# tdt_switch.net
KiCad netlist of a schematic drawn in EAGLE
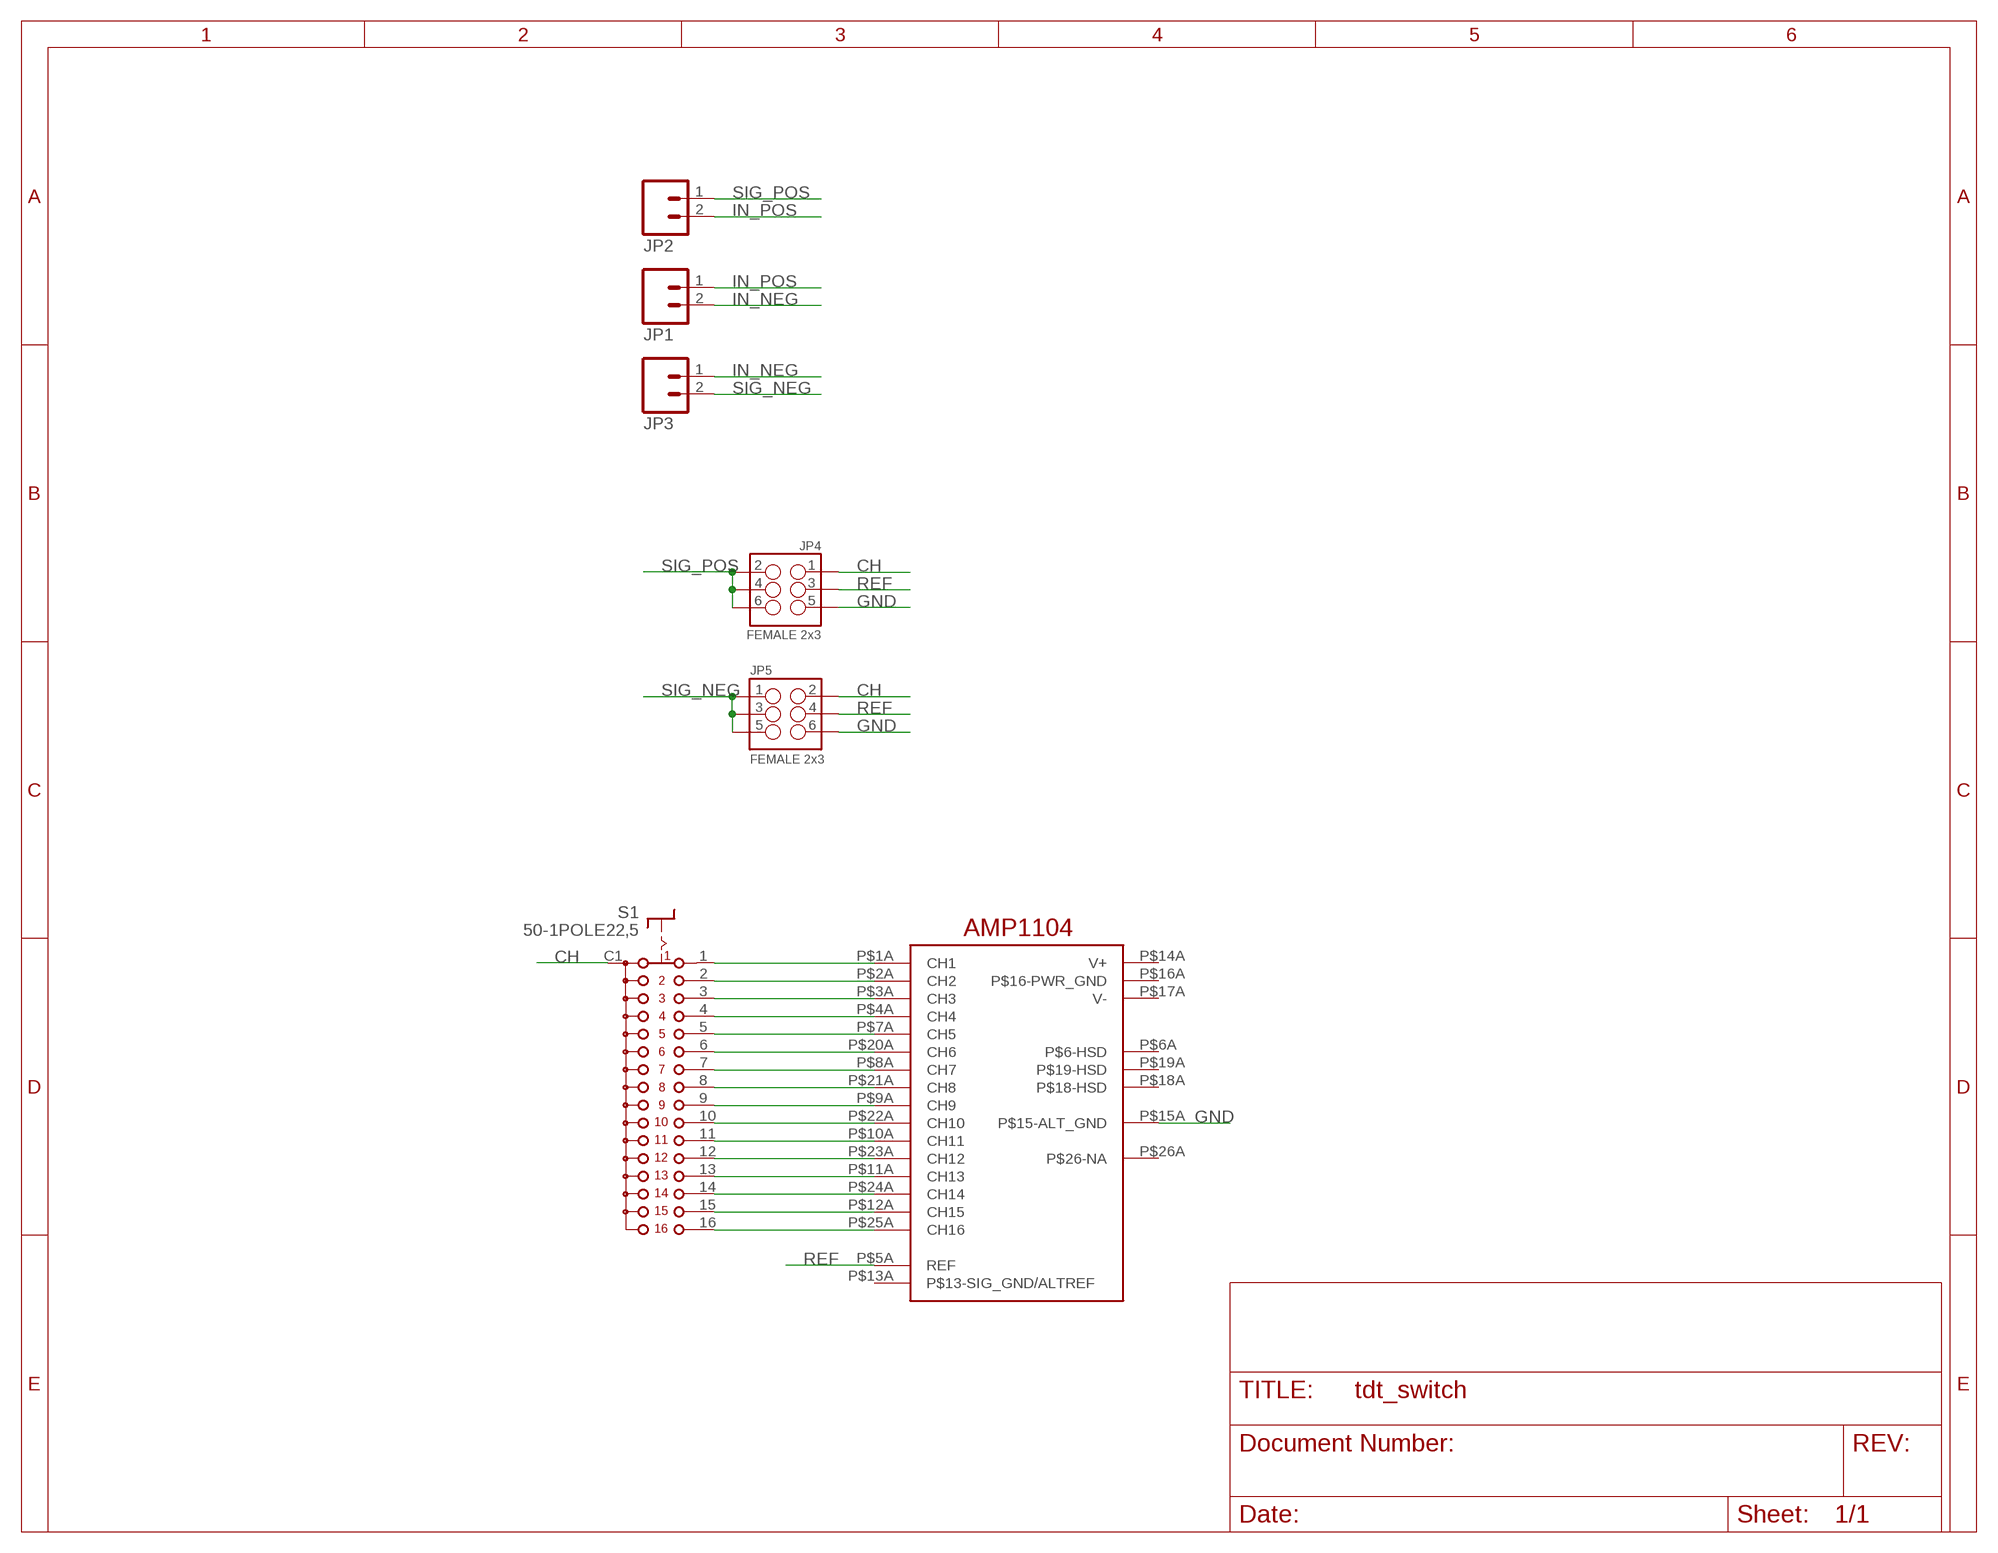
[diagram p0: schematic, sheet 1]

(export (version "E")
  (design (tool "Eeschema 10.0.6"))
  (components
    (comp (ref "JP1")
      (value "M02PTH")
      (footprint "eagle-import:1X02")
      (libsource (lib "eagle-import") (part "M02PTH"))
    )
    (comp (ref "JP2")
      (value "M02PTH")
      (footprint "eagle-import:1X02")
      (libsource (lib "eagle-import") (part "M02PTH"))
    )
    (comp (ref "JP3")
      (value "M02PTH")
      (footprint "eagle-import:1X02")
      (libsource (lib "eagle-import") (part "M02PTH"))
    )
    (comp (ref "JP4")
      (value "FEMALE 2x3")
      (footprint "eagle-import:2X3")
      (libsource (lib "eagle-import") (part "M03X2FEMALE"))
    )
    (comp (ref "JP5")
      (value "FEMALE 2x3")
      (footprint "eagle-import:2X3")
      (libsource (lib "eagle-import") (part "M03X2FEMALE"))
    )
    (comp (ref "S1")
      (value "50-1POLE22,5")
      (footprint "eagle-import:50-1POLE22,5")
      (libsource (lib "eagle-import") (part "50-1POLE22,5"))
    )
    (comp (ref "U$3")
      (value "AMP1104")
      (footprint "eagle-import:AMP1104")
      (libsource (lib "eagle-import") (part "AMP1104"))
    )
  )
  (nets
    (net (code "1") (name "/CH") (class "Default")
      (node (ref "JP4") (pin "1") (pinfunction "1_1") (pintype "bidirectional"))
      (node (ref "JP5") (pin "2") (pinfunction "2_2") (pintype "bidirectional"))
      (node (ref "S1") (pin "C1") (pinfunction "C_C1") (pintype "passive"))
    )
    (net (code "2") (name "/GND") (class "Default")
      (node (ref "JP4") (pin "5") (pinfunction "5_5") (pintype "bidirectional"))
      (node (ref "JP5") (pin "6") (pinfunction "6_6") (pintype "bidirectional"))
      (node (ref "U$3") (pin "P$15A") (pinfunction "P$15-ALT_GND_P$15A") (pintype "bidirectional"))
    )
    (net (code "3") (name "/IN_NEG") (class "Default")
      (node (ref "JP1") (pin "2") (pinfunction "2_2") (pintype "passive"))
      (node (ref "JP3") (pin "1") (pinfunction "1_1") (pintype "passive"))
    )
    (net (code "4") (name "/IN_POS") (class "Default")
      (node (ref "JP1") (pin "1") (pinfunction "1_1") (pintype "passive"))
      (node (ref "JP2") (pin "2") (pinfunction "2_2") (pintype "passive"))
    )
    (net (code "5") (name "/REF") (class "Default")
      (node (ref "JP4") (pin "3") (pinfunction "3_3") (pintype "bidirectional"))
      (node (ref "JP5") (pin "4") (pinfunction "4_4") (pintype "bidirectional"))
      (node (ref "U$3") (pin "P$5A") (pinfunction "REF_P$5A") (pintype "bidirectional"))
    )
    (net (code "6") (name "/SIG_NEG") (class "Default")
      (node (ref "JP3") (pin "2") (pinfunction "2_2") (pintype "passive"))
      (node (ref "JP5") (pin "1") (pinfunction "1_1") (pintype "bidirectional"))
      (node (ref "JP5") (pin "3") (pinfunction "3_3") (pintype "bidirectional"))
      (node (ref "JP5") (pin "5") (pinfunction "5_5") (pintype "bidirectional"))
    )
    (net (code "7") (name "/SIG_POS") (class "Default")
      (node (ref "JP2") (pin "1") (pinfunction "1_1") (pintype "passive"))
      (node (ref "JP4") (pin "2") (pinfunction "2_2") (pintype "bidirectional"))
      (node (ref "JP4") (pin "4") (pinfunction "4_4") (pintype "bidirectional"))
      (node (ref "JP4") (pin "6") (pinfunction "6_6") (pintype "bidirectional"))
    )
    (net (code "8") (name "Net-(U$3-CH1)") (class "Default")
      (node (ref "S1") (pin "1") (pinfunction "1_1") (pintype "passive"))
      (node (ref "U$3") (pin "P$1A") (pinfunction "CH1_P$1A") (pintype "bidirectional"))
    )
    (net (code "9") (name "Net-(U$3-CH2)") (class "Default")
      (node (ref "S1") (pin "2") (pinfunction "2_2") (pintype "passive"))
      (node (ref "U$3") (pin "P$2A") (pinfunction "CH2_P$2A") (pintype "bidirectional"))
    )
    (net (code "10") (name "Net-(U$3-CH3)") (class "Default")
      (node (ref "S1") (pin "3") (pinfunction "3_3") (pintype "passive"))
      (node (ref "U$3") (pin "P$3A") (pinfunction "CH3_P$3A") (pintype "bidirectional"))
    )
    (net (code "11") (name "Net-(U$3-CH4)") (class "Default")
      (node (ref "S1") (pin "4") (pinfunction "4_4") (pintype "passive"))
      (node (ref "U$3") (pin "P$4A") (pinfunction "CH4_P$4A") (pintype "bidirectional"))
    )
    (net (code "12") (name "Net-(U$3-CH5)") (class "Default")
      (node (ref "S1") (pin "5") (pinfunction "5_5") (pintype "passive"))
      (node (ref "U$3") (pin "P$7A") (pinfunction "CH5_P$7A") (pintype "bidirectional"))
    )
    (net (code "13") (name "Net-(U$3-CH6)") (class "Default")
      (node (ref "S1") (pin "6") (pinfunction "6_6") (pintype "passive"))
      (node (ref "U$3") (pin "P$20A") (pinfunction "CH6_P$20A") (pintype "bidirectional"))
    )
    (net (code "14") (name "Net-(U$3-CH7)") (class "Default")
      (node (ref "S1") (pin "7") (pinfunction "7_7") (pintype "passive"))
      (node (ref "U$3") (pin "P$8A") (pinfunction "CH7_P$8A") (pintype "bidirectional"))
    )
    (net (code "15") (name "Net-(U$3-CH8)") (class "Default")
      (node (ref "S1") (pin "8") (pinfunction "8_8") (pintype "passive"))
      (node (ref "U$3") (pin "P$21A") (pinfunction "CH8_P$21A") (pintype "bidirectional"))
    )
    (net (code "16") (name "Net-(U$3-CH9)") (class "Default")
      (node (ref "S1") (pin "9") (pinfunction "9_9") (pintype "passive"))
      (node (ref "U$3") (pin "P$9A") (pinfunction "CH9_P$9A") (pintype "bidirectional"))
    )
    (net (code "17") (name "Net-(U$3-CH10)") (class "Default")
      (node (ref "S1") (pin "10") (pinfunction "10_10") (pintype "passive"))
      (node (ref "U$3") (pin "P$22A") (pinfunction "CH10_P$22A") (pintype "bidirectional"))
    )
    (net (code "18") (name "Net-(U$3-CH11)") (class "Default")
      (node (ref "S1") (pin "11") (pinfunction "11_11") (pintype "passive"))
      (node (ref "U$3") (pin "P$10A") (pinfunction "CH11_P$10A") (pintype "bidirectional"))
    )
    (net (code "19") (name "Net-(U$3-CH12)") (class "Default")
      (node (ref "S1") (pin "12") (pinfunction "12_12") (pintype "passive"))
      (node (ref "U$3") (pin "P$23A") (pinfunction "CH12_P$23A") (pintype "bidirectional"))
    )
    (net (code "20") (name "Net-(U$3-CH13)") (class "Default")
      (node (ref "S1") (pin "13") (pinfunction "13_13") (pintype "passive"))
      (node (ref "U$3") (pin "P$11A") (pinfunction "CH13_P$11A") (pintype "bidirectional"))
    )
    (net (code "21") (name "Net-(U$3-CH14)") (class "Default")
      (node (ref "S1") (pin "14") (pinfunction "14_14") (pintype "passive"))
      (node (ref "U$3") (pin "P$24A") (pinfunction "CH14_P$24A") (pintype "bidirectional"))
    )
    (net (code "22") (name "Net-(U$3-CH15)") (class "Default")
      (node (ref "S1") (pin "15") (pinfunction "15_15") (pintype "passive"))
      (node (ref "U$3") (pin "P$12A") (pinfunction "CH15_P$12A") (pintype "bidirectional"))
    )
    (net (code "23") (name "Net-(U$3-CH16)") (class "Default")
      (node (ref "S1") (pin "16") (pinfunction "16_16") (pintype "passive"))
      (node (ref "U$3") (pin "P$25A") (pinfunction "CH16_P$25A") (pintype "bidirectional"))
    )
    (net (code "24") (name "unconnected-(U$3-P$6-HSD-PadP$6A)") (class "Default")
      (node (ref "U$3") (pin "P$6A") (pinfunction "P$6-HSD_P$6A") (pintype "bidirectional"))
    )
    (net (code "25") (name "unconnected-(U$3-P$13-SIG_GND{slash}ALTREF-PadP$13A)") (class "Default")
      (node (ref "U$3") (pin "P$13A") (pinfunction "P$13-SIG_GND/ALTREF_P$13A") (pintype "bidirectional"))
    )
    (net (code "26") (name "unconnected-(U$3-P$16-PWR_GND-PadP$16A)") (class "Default")
      (node (ref "U$3") (pin "P$16A") (pinfunction "P$16-PWR_GND_P$16A") (pintype "bidirectional"))
    )
    (net (code "27") (name "unconnected-(U$3-P$18-HSD-PadP$18A)") (class "Default")
      (node (ref "U$3") (pin "P$18A") (pinfunction "P$18-HSD_P$18A") (pintype "bidirectional"))
    )
    (net (code "28") (name "unconnected-(U$3-P$19-HSD-PadP$19A)") (class "Default")
      (node (ref "U$3") (pin "P$19A") (pinfunction "P$19-HSD_P$19A") (pintype "bidirectional"))
    )
    (net (code "29") (name "unconnected-(U$3-P$26-NA-PadP$26A)") (class "Default")
      (node (ref "U$3") (pin "P$26A") (pinfunction "P$26-NA_P$26A") (pintype "bidirectional"))
    )
    (net (code "30") (name "unconnected-(U$3-V+-PadP$14A)") (class "Default")
      (node (ref "U$3") (pin "P$14A") (pinfunction "V+_P$14A") (pintype "bidirectional"))
    )
    (net (code "31") (name "unconnected-(U$3-V--PadP$17A)") (class "Default")
      (node (ref "U$3") (pin "P$17A") (pinfunction "V-_P$17A") (pintype "bidirectional"))
    )
  )
)
